# DS18B20.net
KiCad netlist of a schematic drawn in Altium Designer
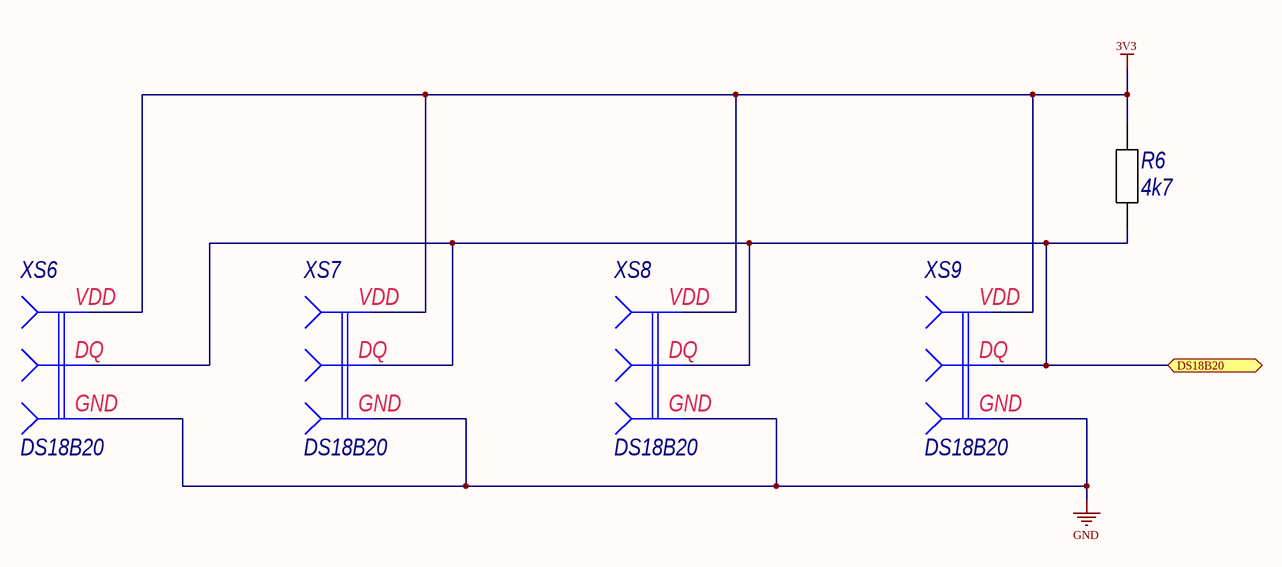
[diagram p0: DS18B20.SchDoc]

(export (version "E")
  (design (tool "Eeschema 10.0.6"))
  (components
    (comp (ref "R6")
      (value "4k7")
      (footprint "C0805R")
      (fields (field (name "PUBLISHER") "Andrew Danich"))
      (libsource (lib "PA_control_board") (part "R0805"))
    )
    (comp (ref "XS6")
      (value "DS18B20")
      (footprint "YX-XH-3")
      (fields (field (name "PUBLISHER") "Andrew Danich"))
      (libsource (lib "PA_control_board") (part "DS18B20"))
    )
    (comp (ref "XS7")
      (value "DS18B20")
      (footprint "YX-XH-3")
      (fields (field (name "PUBLISHER") "Andrew Danich"))
      (libsource (lib "PA_control_board") (part "DS18B20"))
    )
    (comp (ref "XS8")
      (value "DS18B20")
      (footprint "YX-XH-3")
      (fields (field (name "PUBLISHER") "Andrew Danich"))
      (libsource (lib "PA_control_board") (part "DS18B20"))
    )
    (comp (ref "XS9")
      (value "DS18B20")
      (footprint "YX-XH-3")
      (fields (field (name "PUBLISHER") "Andrew Danich"))
      (libsource (lib "PA_control_board") (part "DS18B20"))
    )
  )
  (nets
    (net (code "1") (name "/DS18B20") (class "Default")
      (node (ref "R6") (pin "2") (pinfunction "2_2") (pintype "passive"))
      (node (ref "XS6") (pin "2") (pintype "passive"))
      (node (ref "XS7") (pin "2") (pintype "passive"))
      (node (ref "XS8") (pin "2") (pintype "passive"))
      (node (ref "XS9") (pin "2") (pintype "passive"))
    )
    (net (code "2") (name "3V3") (class "Default")
      (node (ref "R6") (pin "1") (pinfunction "1_1") (pintype "passive"))
      (node (ref "XS6") (pin "1") (pintype "passive"))
      (node (ref "XS7") (pin "1") (pintype "passive"))
      (node (ref "XS8") (pin "1") (pintype "passive"))
      (node (ref "XS9") (pin "1") (pintype "passive"))
    )
    (net (code "3") (name "GND") (class "Default")
      (node (ref "XS6") (pin "3") (pintype "passive"))
      (node (ref "XS7") (pin "3") (pintype "passive"))
      (node (ref "XS8") (pin "3") (pintype "passive"))
      (node (ref "XS9") (pin "3") (pintype "passive"))
    )
  )
)
